# candle-.net
KiCad netlist of a schematic drawn in EAGLE
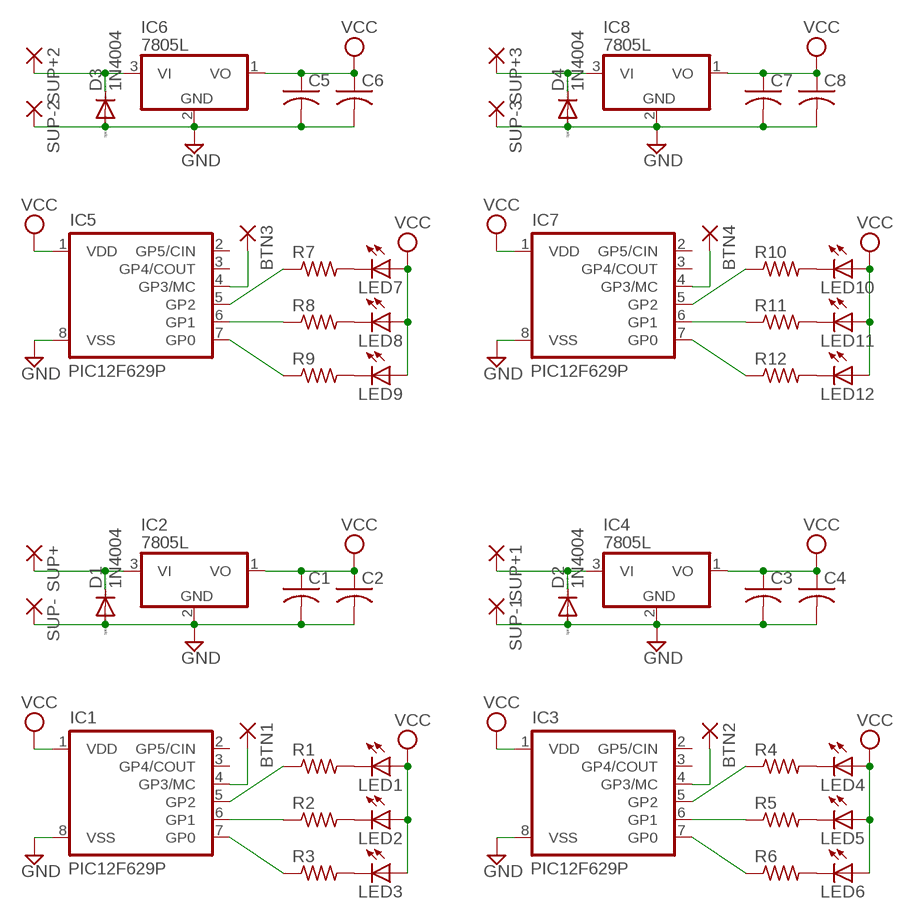
[diagram p0: schematic, sheet 1]

(export (version "E")
  (design (tool "Eeschema 10.0.6"))
  (components
    (comp (ref "BTN1")
      (value "1,6/0,8")
      (footprint "eagle-import:1,6_0,8")
      (libsource (lib "eagle-import") (part "1,6/0,8"))
    )
    (comp (ref "BTN2")
      (value "1,6/0,8")
      (footprint "eagle-import:1,6_0,8")
      (libsource (lib "eagle-import") (part "1,6/0,8"))
    )
    (comp (ref "BTN3")
      (value "1,6/0,8")
      (footprint "eagle-import:1,6_0,8")
      (libsource (lib "eagle-import") (part "1,6/0,8"))
    )
    (comp (ref "BTN4")
      (value "1,6/0,8")
      (footprint "eagle-import:1,6_0,8")
      (libsource (lib "eagle-import") (part "1,6/0,8"))
    )
    (comp (ref "C1")
      (value "C-US025-025X050")
      (footprint "eagle-import:C025-025X050")
      (libsource (lib "eagle-import") (part "C-US025-025X050"))
    )
    (comp (ref "C2")
      (value "C-US025-025X050")
      (footprint "eagle-import:C025-025X050")
      (libsource (lib "eagle-import") (part "C-US025-025X050"))
    )
    (comp (ref "C3")
      (value "C-US025-025X050")
      (footprint "eagle-import:C025-025X050")
      (libsource (lib "eagle-import") (part "C-US025-025X050"))
    )
    (comp (ref "C4")
      (value "C-US025-025X050")
      (footprint "eagle-import:C025-025X050")
      (libsource (lib "eagle-import") (part "C-US025-025X050"))
    )
    (comp (ref "C5")
      (value "C-US025-025X050")
      (footprint "eagle-import:C025-025X050")
      (libsource (lib "eagle-import") (part "C-US025-025X050"))
    )
    (comp (ref "C6")
      (value "C-US025-025X050")
      (footprint "eagle-import:C025-025X050")
      (libsource (lib "eagle-import") (part "C-US025-025X050"))
    )
    (comp (ref "C7")
      (value "C-US025-025X050")
      (footprint "eagle-import:C025-025X050")
      (libsource (lib "eagle-import") (part "C-US025-025X050"))
    )
    (comp (ref "C8")
      (value "C-US025-025X050")
      (footprint "eagle-import:C025-025X050")
      (libsource (lib "eagle-import") (part "C-US025-025X050"))
    )
    (comp (ref "D1")
      (value "1N4004")
      (footprint "eagle-import:DO41-10")
      (libsource (lib "eagle-import") (part "1N4004"))
    )
    (comp (ref "D2")
      (value "1N4004")
      (footprint "eagle-import:DO41-10")
      (libsource (lib "eagle-import") (part "1N4004"))
    )
    (comp (ref "D3")
      (value "1N4004")
      (footprint "eagle-import:DO41-10")
      (libsource (lib "eagle-import") (part "1N4004"))
    )
    (comp (ref "D4")
      (value "1N4004")
      (footprint "eagle-import:DO41-10")
      (libsource (lib "eagle-import") (part "1N4004"))
    )
    (comp (ref "IC1")
      (value "PIC12F629P")
      (footprint "eagle-import:DIL8")
      (fields (field (name "MF") "MICROCHIP") (field (name "MPN") "PIC12C671-10/P"))
      (libsource (lib "eagle-import") (part "PIC12C?P671"))
    )
    (comp (ref "IC2")
      (value "7805L")
      (footprint "eagle-import:TO92")
      (libsource (lib "eagle-import") (part "78L05"))
    )
    (comp (ref "IC3")
      (value "PIC12F629P")
      (footprint "eagle-import:DIL8")
      (fields (field (name "MF") "MICROCHIP") (field (name "MPN") "PIC12C671-10/P"))
      (libsource (lib "eagle-import") (part "PIC12C?P671"))
    )
    (comp (ref "IC4")
      (value "7805L")
      (footprint "eagle-import:TO92")
      (libsource (lib "eagle-import") (part "78L05"))
    )
    (comp (ref "IC5")
      (value "PIC12F629P")
      (footprint "eagle-import:DIL8")
      (fields (field (name "MF") "MICROCHIP") (field (name "MPN") "PIC12C671-10/P"))
      (libsource (lib "eagle-import") (part "PIC12C?P671"))
    )
    (comp (ref "IC6")
      (value "7805L")
      (footprint "eagle-import:TO92")
      (libsource (lib "eagle-import") (part "78L05"))
    )
    (comp (ref "IC7")
      (value "PIC12F629P")
      (footprint "eagle-import:DIL8")
      (fields (field (name "MF") "MICROCHIP") (field (name "MPN") "PIC12C671-10/P"))
      (libsource (lib "eagle-import") (part "PIC12C?P671"))
    )
    (comp (ref "IC8")
      (value "7805L")
      (footprint "eagle-import:TO92")
      (libsource (lib "eagle-import") (part "78L05"))
    )
    (comp (ref "LED1")
      (value "LED5MM")
      (footprint "eagle-import:LED5MM")
      (libsource (lib "eagle-import") (part "LED5MM"))
    )
    (comp (ref "LED2")
      (value "LED5MM")
      (footprint "eagle-import:LED5MM")
      (libsource (lib "eagle-import") (part "LED5MM"))
    )
    (comp (ref "LED3")
      (value "LED5MM")
      (footprint "eagle-import:LED5MM")
      (libsource (lib "eagle-import") (part "LED5MM"))
    )
    (comp (ref "LED4")
      (value "LED5MM")
      (footprint "eagle-import:LED5MM")
      (libsource (lib "eagle-import") (part "LED5MM"))
    )
    (comp (ref "LED5")
      (value "LED5MM")
      (footprint "eagle-import:LED5MM")
      (libsource (lib "eagle-import") (part "LED5MM"))
    )
    (comp (ref "LED6")
      (value "LED5MM")
      (footprint "eagle-import:LED5MM")
      (libsource (lib "eagle-import") (part "LED5MM"))
    )
    (comp (ref "LED7")
      (value "LED5MM")
      (footprint "eagle-import:LED5MM")
      (libsource (lib "eagle-import") (part "LED5MM"))
    )
    (comp (ref "LED8")
      (value "LED5MM")
      (footprint "eagle-import:LED5MM")
      (libsource (lib "eagle-import") (part "LED5MM"))
    )
    (comp (ref "LED9")
      (value "LED5MM")
      (footprint "eagle-import:LED5MM")
      (libsource (lib "eagle-import") (part "LED5MM"))
    )
    (comp (ref "LED10")
      (value "LED5MM")
      (footprint "eagle-import:LED5MM")
      (libsource (lib "eagle-import") (part "LED5MM"))
    )
    (comp (ref "LED11")
      (value "LED5MM")
      (footprint "eagle-import:LED5MM")
      (libsource (lib "eagle-import") (part "LED5MM"))
    )
    (comp (ref "LED12")
      (value "LED5MM")
      (footprint "eagle-import:LED5MM")
      (libsource (lib "eagle-import") (part "LED5MM"))
    )
    (comp (ref "R1")
      (value "R-US_0204/7")
      (footprint "eagle-import:0204_7")
      (libsource (lib "eagle-import") (part "R-US_0204/7"))
    )
    (comp (ref "R2")
      (value "R-US_0204/7")
      (footprint "eagle-import:0204_7")
      (libsource (lib "eagle-import") (part "R-US_0204/7"))
    )
    (comp (ref "R3")
      (value "R-US_0204/7")
      (footprint "eagle-import:0204_7")
      (libsource (lib "eagle-import") (part "R-US_0204/7"))
    )
    (comp (ref "R4")
      (value "R-US_0204/7")
      (footprint "eagle-import:0204_7")
      (libsource (lib "eagle-import") (part "R-US_0204/7"))
    )
    (comp (ref "R5")
      (value "R-US_0204/7")
      (footprint "eagle-import:0204_7")
      (libsource (lib "eagle-import") (part "R-US_0204/7"))
    )
    (comp (ref "R6")
      (value "R-US_0204/7")
      (footprint "eagle-import:0204_7")
      (libsource (lib "eagle-import") (part "R-US_0204/7"))
    )
    (comp (ref "R7")
      (value "R-US_0204/7")
      (footprint "eagle-import:0204_7")
      (libsource (lib "eagle-import") (part "R-US_0204/7"))
    )
    (comp (ref "R8")
      (value "R-US_0204/7")
      (footprint "eagle-import:0204_7")
      (libsource (lib "eagle-import") (part "R-US_0204/7"))
    )
    (comp (ref "R9")
      (value "R-US_0204/7")
      (footprint "eagle-import:0204_7")
      (libsource (lib "eagle-import") (part "R-US_0204/7"))
    )
    (comp (ref "R10")
      (value "R-US_0204/7")
      (footprint "eagle-import:0204_7")
      (libsource (lib "eagle-import") (part "R-US_0204/7"))
    )
    (comp (ref "R11")
      (value "R-US_0204/7")
      (footprint "eagle-import:0204_7")
      (libsource (lib "eagle-import") (part "R-US_0204/7"))
    )
    (comp (ref "R12")
      (value "R-US_0204/7")
      (footprint "eagle-import:0204_7")
      (libsource (lib "eagle-import") (part "R-US_0204/7"))
    )
    (comp (ref "SUP+")
      (value "1,6/0,8")
      (footprint "eagle-import:1,6_0,8")
      (libsource (lib "eagle-import") (part "1,6/0,8"))
    )
    (comp (ref "SUP+1")
      (value "1,6/0,8")
      (footprint "eagle-import:1,6_0,8")
      (libsource (lib "eagle-import") (part "1,6/0,8"))
    )
    (comp (ref "SUP+2")
      (value "1,6/0,8")
      (footprint "eagle-import:1,6_0,8")
      (libsource (lib "eagle-import") (part "1,6/0,8"))
    )
    (comp (ref "SUP+3")
      (value "1,6/0,8")
      (footprint "eagle-import:1,6_0,8")
      (libsource (lib "eagle-import") (part "1,6/0,8"))
    )
    (comp (ref "SUP-")
      (value "1,6/0,8")
      (footprint "eagle-import:1,6_0,8")
      (libsource (lib "eagle-import") (part "1,6/0,8"))
    )
    (comp (ref "SUP-1")
      (value "1,6/0,8")
      (footprint "eagle-import:1,6_0,8")
      (libsource (lib "eagle-import") (part "1,6/0,8"))
    )
    (comp (ref "SUP-2")
      (value "1,6/0,8")
      (footprint "eagle-import:1,6_0,8")
      (libsource (lib "eagle-import") (part "1,6/0,8"))
    )
    (comp (ref "SUP-3")
      (value "1,6/0,8")
      (footprint "eagle-import:1,6_0,8")
      (libsource (lib "eagle-import") (part "1,6/0,8"))
    )
  )
  (nets
    (net (code "1") (name "GND") (class "Default")
      (node (ref "C1") (pin "2") (pinfunction "2_2") (pintype "passive"))
      (node (ref "C2") (pin "2") (pinfunction "2_2") (pintype "passive"))
      (node (ref "C3") (pin "2") (pinfunction "2_2") (pintype "passive"))
      (node (ref "C4") (pin "2") (pinfunction "2_2") (pintype "passive"))
      (node (ref "C5") (pin "2") (pinfunction "2_2") (pintype "passive"))
      (node (ref "C6") (pin "2") (pinfunction "2_2") (pintype "passive"))
      (node (ref "C7") (pin "2") (pinfunction "2_2") (pintype "passive"))
      (node (ref "C8") (pin "2") (pinfunction "2_2") (pintype "passive"))
      (node (ref "D1") (pin "A") (pinfunction "A_A") (pintype "passive"))
      (node (ref "D2") (pin "A") (pinfunction "A_A") (pintype "passive"))
      (node (ref "D3") (pin "A") (pinfunction "A_A") (pintype "passive"))
      (node (ref "D4") (pin "A") (pinfunction "A_A") (pintype "passive"))
      (node (ref "IC1") (pin "8") (pinfunction "VSS_8") (pintype "power_in"))
      (node (ref "IC2") (pin "2") (pinfunction "GND_2") (pintype "passive"))
      (node (ref "IC3") (pin "8") (pinfunction "VSS_8") (pintype "power_in"))
      (node (ref "IC4") (pin "2") (pinfunction "GND_2") (pintype "passive"))
      (node (ref "IC5") (pin "8") (pinfunction "VSS_8") (pintype "power_in"))
      (node (ref "IC6") (pin "2") (pinfunction "GND_2") (pintype "passive"))
      (node (ref "IC7") (pin "8") (pinfunction "VSS_8") (pintype "power_in"))
      (node (ref "IC8") (pin "2") (pinfunction "GND_2") (pintype "passive"))
      (node (ref "SUP-") (pin "1") (pinfunction "P_1") (pintype "passive"))
      (node (ref "SUP-1") (pin "1") (pinfunction "P_1") (pintype "passive"))
      (node (ref "SUP-2") (pin "1") (pinfunction "P_1") (pintype "passive"))
      (node (ref "SUP-3") (pin "1") (pinfunction "P_1") (pintype "passive"))
    )
    (net (code "2") (name "Net-(BTN1-P)") (class "Default")
      (node (ref "BTN1") (pin "1") (pinfunction "P_1") (pintype "passive"))
      (node (ref "IC1") (pin "4") (pinfunction "GP3/MC_4") (pintype "input"))
    )
    (net (code "3") (name "Net-(BTN2-P)") (class "Default")
      (node (ref "BTN2") (pin "1") (pinfunction "P_1") (pintype "passive"))
      (node (ref "IC3") (pin "4") (pinfunction "GP3/MC_4") (pintype "input"))
    )
    (net (code "4") (name "Net-(BTN3-P)") (class "Default")
      (node (ref "BTN3") (pin "1") (pinfunction "P_1") (pintype "passive"))
      (node (ref "IC5") (pin "4") (pinfunction "GP3/MC_4") (pintype "input"))
    )
    (net (code "5") (name "Net-(BTN4-P)") (class "Default")
      (node (ref "BTN4") (pin "1") (pinfunction "P_1") (pintype "passive"))
      (node (ref "IC7") (pin "4") (pinfunction "GP3/MC_4") (pintype "input"))
    )
    (net (code "6") (name "Net-(IC1-GP0)") (class "Default")
      (node (ref "IC1") (pin "7") (pinfunction "GP0_7") (pintype "bidirectional"))
      (node (ref "R3") (pin "1") (pinfunction "1_1") (pintype "passive"))
    )
    (net (code "7") (name "Net-(IC1-GP1)") (class "Default")
      (node (ref "IC1") (pin "6") (pinfunction "GP1_6") (pintype "bidirectional"))
      (node (ref "R2") (pin "1") (pinfunction "1_1") (pintype "passive"))
    )
    (net (code "8") (name "Net-(IC1-GP2)") (class "Default")
      (node (ref "IC1") (pin "5") (pinfunction "GP2_5") (pintype "bidirectional"))
      (node (ref "R1") (pin "1") (pinfunction "1_1") (pintype "passive"))
    )
    (net (code "9") (name "Net-(IC2-VI)") (class "Default")
      (node (ref "D1") (pin "C") (pinfunction "C_C") (pintype "passive"))
      (node (ref "IC2") (pin "3") (pinfunction "VI_3") (pintype "input"))
      (node (ref "SUP+") (pin "1") (pinfunction "P_1") (pintype "passive"))
    )
    (net (code "10") (name "Net-(IC3-GP0)") (class "Default")
      (node (ref "IC3") (pin "7") (pinfunction "GP0_7") (pintype "bidirectional"))
      (node (ref "R6") (pin "1") (pinfunction "1_1") (pintype "passive"))
    )
    (net (code "11") (name "Net-(IC3-GP1)") (class "Default")
      (node (ref "IC3") (pin "6") (pinfunction "GP1_6") (pintype "bidirectional"))
      (node (ref "R5") (pin "1") (pinfunction "1_1") (pintype "passive"))
    )
    (net (code "12") (name "Net-(IC3-GP2)") (class "Default")
      (node (ref "IC3") (pin "5") (pinfunction "GP2_5") (pintype "bidirectional"))
      (node (ref "R4") (pin "1") (pinfunction "1_1") (pintype "passive"))
    )
    (net (code "13") (name "Net-(IC4-VI)") (class "Default")
      (node (ref "D2") (pin "C") (pinfunction "C_C") (pintype "passive"))
      (node (ref "IC4") (pin "3") (pinfunction "VI_3") (pintype "input"))
      (node (ref "SUP+1") (pin "1") (pinfunction "P_1") (pintype "passive"))
    )
    (net (code "14") (name "Net-(IC5-GP0)") (class "Default")
      (node (ref "IC5") (pin "7") (pinfunction "GP0_7") (pintype "bidirectional"))
      (node (ref "R9") (pin "1") (pinfunction "1_1") (pintype "passive"))
    )
    (net (code "15") (name "Net-(IC5-GP1)") (class "Default")
      (node (ref "IC5") (pin "6") (pinfunction "GP1_6") (pintype "bidirectional"))
      (node (ref "R8") (pin "1") (pinfunction "1_1") (pintype "passive"))
    )
    (net (code "16") (name "Net-(IC5-GP2)") (class "Default")
      (node (ref "IC5") (pin "5") (pinfunction "GP2_5") (pintype "bidirectional"))
      (node (ref "R7") (pin "1") (pinfunction "1_1") (pintype "passive"))
    )
    (net (code "17") (name "Net-(IC6-VI)") (class "Default")
      (node (ref "D3") (pin "C") (pinfunction "C_C") (pintype "passive"))
      (node (ref "IC6") (pin "3") (pinfunction "VI_3") (pintype "input"))
      (node (ref "SUP+2") (pin "1") (pinfunction "P_1") (pintype "passive"))
    )
    (net (code "18") (name "Net-(IC7-GP0)") (class "Default")
      (node (ref "IC7") (pin "7") (pinfunction "GP0_7") (pintype "bidirectional"))
      (node (ref "R12") (pin "1") (pinfunction "1_1") (pintype "passive"))
    )
    (net (code "19") (name "Net-(IC7-GP1)") (class "Default")
      (node (ref "IC7") (pin "6") (pinfunction "GP1_6") (pintype "bidirectional"))
      (node (ref "R11") (pin "1") (pinfunction "1_1") (pintype "passive"))
    )
    (net (code "20") (name "Net-(IC7-GP2)") (class "Default")
      (node (ref "IC7") (pin "5") (pinfunction "GP2_5") (pintype "bidirectional"))
      (node (ref "R10") (pin "1") (pinfunction "1_1") (pintype "passive"))
    )
    (net (code "21") (name "Net-(IC8-VI)") (class "Default")
      (node (ref "D4") (pin "C") (pinfunction "C_C") (pintype "passive"))
      (node (ref "IC8") (pin "3") (pinfunction "VI_3") (pintype "input"))
      (node (ref "SUP+3") (pin "1") (pinfunction "P_1") (pintype "passive"))
    )
    (net (code "22") (name "Net-(LED1-C)") (class "Default")
      (node (ref "LED1") (pin "K") (pinfunction "C_K") (pintype "passive"))
      (node (ref "R1") (pin "2") (pinfunction "2_2") (pintype "passive"))
    )
    (net (code "23") (name "Net-(LED2-C)") (class "Default")
      (node (ref "LED2") (pin "K") (pinfunction "C_K") (pintype "passive"))
      (node (ref "R2") (pin "2") (pinfunction "2_2") (pintype "passive"))
    )
    (net (code "24") (name "Net-(LED3-C)") (class "Default")
      (node (ref "LED3") (pin "K") (pinfunction "C_K") (pintype "passive"))
      (node (ref "R3") (pin "2") (pinfunction "2_2") (pintype "passive"))
    )
    (net (code "25") (name "Net-(LED4-C)") (class "Default")
      (node (ref "LED4") (pin "K") (pinfunction "C_K") (pintype "passive"))
      (node (ref "R4") (pin "2") (pinfunction "2_2") (pintype "passive"))
    )
    (net (code "26") (name "Net-(LED5-C)") (class "Default")
      (node (ref "LED5") (pin "K") (pinfunction "C_K") (pintype "passive"))
      (node (ref "R5") (pin "2") (pinfunction "2_2") (pintype "passive"))
    )
    (net (code "27") (name "Net-(LED6-C)") (class "Default")
      (node (ref "LED6") (pin "K") (pinfunction "C_K") (pintype "passive"))
      (node (ref "R6") (pin "2") (pinfunction "2_2") (pintype "passive"))
    )
    (net (code "28") (name "Net-(LED7-C)") (class "Default")
      (node (ref "LED7") (pin "K") (pinfunction "C_K") (pintype "passive"))
      (node (ref "R7") (pin "2") (pinfunction "2_2") (pintype "passive"))
    )
    (net (code "29") (name "Net-(LED8-C)") (class "Default")
      (node (ref "LED8") (pin "K") (pinfunction "C_K") (pintype "passive"))
      (node (ref "R8") (pin "2") (pinfunction "2_2") (pintype "passive"))
    )
    (net (code "30") (name "Net-(LED9-C)") (class "Default")
      (node (ref "LED9") (pin "K") (pinfunction "C_K") (pintype "passive"))
      (node (ref "R9") (pin "2") (pinfunction "2_2") (pintype "passive"))
    )
    (net (code "31") (name "Net-(LED10-C)") (class "Default")
      (node (ref "LED10") (pin "K") (pinfunction "C_K") (pintype "passive"))
      (node (ref "R10") (pin "2") (pinfunction "2_2") (pintype "passive"))
    )
    (net (code "32") (name "Net-(LED11-C)") (class "Default")
      (node (ref "LED11") (pin "K") (pinfunction "C_K") (pintype "passive"))
      (node (ref "R11") (pin "2") (pinfunction "2_2") (pintype "passive"))
    )
    (net (code "33") (name "Net-(LED12-C)") (class "Default")
      (node (ref "LED12") (pin "K") (pinfunction "C_K") (pintype "passive"))
      (node (ref "R12") (pin "2") (pinfunction "2_2") (pintype "passive"))
    )
    (net (code "34") (name "VCC") (class "Default")
      (node (ref "C1") (pin "1") (pinfunction "1_1") (pintype "passive"))
      (node (ref "C2") (pin "1") (pinfunction "1_1") (pintype "passive"))
      (node (ref "C3") (pin "1") (pinfunction "1_1") (pintype "passive"))
      (node (ref "C4") (pin "1") (pinfunction "1_1") (pintype "passive"))
      (node (ref "C5") (pin "1") (pinfunction "1_1") (pintype "passive"))
      (node (ref "C6") (pin "1") (pinfunction "1_1") (pintype "passive"))
      (node (ref "C7") (pin "1") (pinfunction "1_1") (pintype "passive"))
      (node (ref "C8") (pin "1") (pinfunction "1_1") (pintype "passive"))
      (node (ref "IC1") (pin "1") (pinfunction "VDD_1") (pintype "power_in"))
      (node (ref "IC2") (pin "1") (pinfunction "VO_1") (pintype "passive"))
      (node (ref "IC3") (pin "1") (pinfunction "VDD_1") (pintype "power_in"))
      (node (ref "IC4") (pin "1") (pinfunction "VO_1") (pintype "passive"))
      (node (ref "IC5") (pin "1") (pinfunction "VDD_1") (pintype "power_in"))
      (node (ref "IC6") (pin "1") (pinfunction "VO_1") (pintype "passive"))
      (node (ref "IC7") (pin "1") (pinfunction "VDD_1") (pintype "power_in"))
      (node (ref "IC8") (pin "1") (pinfunction "VO_1") (pintype "passive"))
      (node (ref "LED1") (pin "A") (pinfunction "A_A") (pintype "passive"))
      (node (ref "LED10") (pin "A") (pinfunction "A_A") (pintype "passive"))
      (node (ref "LED11") (pin "A") (pinfunction "A_A") (pintype "passive"))
      (node (ref "LED12") (pin "A") (pinfunction "A_A") (pintype "passive"))
      (node (ref "LED2") (pin "A") (pinfunction "A_A") (pintype "passive"))
      (node (ref "LED3") (pin "A") (pinfunction "A_A") (pintype "passive"))
      (node (ref "LED4") (pin "A") (pinfunction "A_A") (pintype "passive"))
      (node (ref "LED5") (pin "A") (pinfunction "A_A") (pintype "passive"))
      (node (ref "LED6") (pin "A") (pinfunction "A_A") (pintype "passive"))
      (node (ref "LED7") (pin "A") (pinfunction "A_A") (pintype "passive"))
      (node (ref "LED8") (pin "A") (pinfunction "A_A") (pintype "passive"))
      (node (ref "LED9") (pin "A") (pinfunction "A_A") (pintype "passive"))
    )
    (net (code "35") (name "unconnected-(IC1-GP4{slash}COUT-Pad3)") (class "Default")
      (node (ref "IC1") (pin "3") (pinfunction "GP4/COUT_3") (pintype "bidirectional"))
    )
    (net (code "36") (name "unconnected-(IC1-GP5{slash}CIN-Pad2)") (class "Default")
      (node (ref "IC1") (pin "2") (pinfunction "GP5/CIN_2") (pintype "bidirectional"))
    )
    (net (code "37") (name "unconnected-(IC3-GP4{slash}COUT-Pad3)") (class "Default")
      (node (ref "IC3") (pin "3") (pinfunction "GP4/COUT_3") (pintype "bidirectional"))
    )
    (net (code "38") (name "unconnected-(IC3-GP5{slash}CIN-Pad2)") (class "Default")
      (node (ref "IC3") (pin "2") (pinfunction "GP5/CIN_2") (pintype "bidirectional"))
    )
    (net (code "39") (name "unconnected-(IC5-GP4{slash}COUT-Pad3)") (class "Default")
      (node (ref "IC5") (pin "3") (pinfunction "GP4/COUT_3") (pintype "bidirectional"))
    )
    (net (code "40") (name "unconnected-(IC5-GP5{slash}CIN-Pad2)") (class "Default")
      (node (ref "IC5") (pin "2") (pinfunction "GP5/CIN_2") (pintype "bidirectional"))
    )
    (net (code "41") (name "unconnected-(IC7-GP4{slash}COUT-Pad3)") (class "Default")
      (node (ref "IC7") (pin "3") (pinfunction "GP4/COUT_3") (pintype "bidirectional"))
    )
    (net (code "42") (name "unconnected-(IC7-GP5{slash}CIN-Pad2)") (class "Default")
      (node (ref "IC7") (pin "2") (pinfunction "GP5/CIN_2") (pintype "bidirectional"))
    )
  )
)
